# 7_Jetson_Nano_P3.net
KiCad netlist of a schematic drawn in Altium Designer
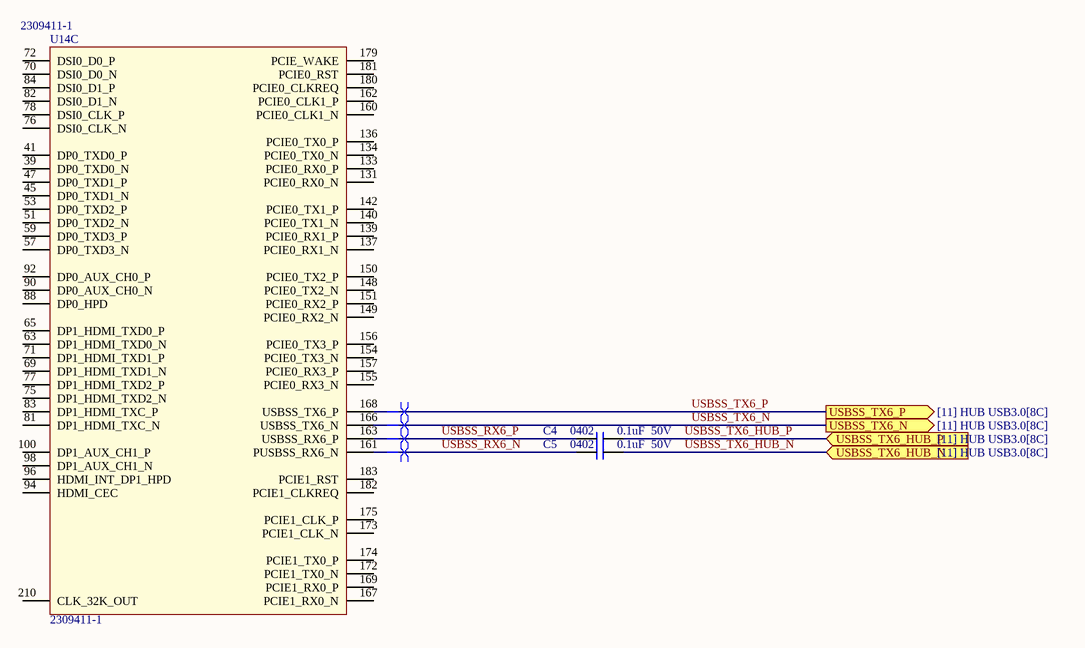
[diagram p0: [7] Jetson Nano P3.SchDoc]

(export (version "E")
  (design (tool "Eeschema 10.0.6"))
  (components
    (comp (ref "C4")
      (value "0.1uF")
      (footprint "C0402M")
      (description "CAP CER 0.1UF 50V X7R 0402")
      (fields
        (field (name "MANUFACTURER") "Murata")
        (field (name "MANUFACTURER PART NUMBER") "GRM155R71H104KE14D")
        (field (name "CASE/PACKAGE") "0402")
        (field (name "VOLTAGE") "50V")
      )
      (libsource (lib "CommonLib") (part "CAP_CER"))
    )
    (comp (ref "C5")
      (value "0.1uF")
      (footprint "C0402M")
      (description "CAP CER 0.1UF 50V X7R 0402")
      (fields
        (field (name "MANUFACTURER") "Murata")
        (field (name "MANUFACTURER PART NUMBER") "GRM155R71H104KE14D")
        (field (name "CASE/PACKAGE") "0402")
        (field (name "VOLTAGE") "50V")
      )
      (libsource (lib "CommonLib") (part "CAP_CER"))
    )
    (comp (ref "U14")
      (value "2309411-1")
      (footprint "2309411-1")
      (description "DDR4 SODIMM 260P 8.0H STD")
      (fields
        (field (name "MANUFACTURER") "TE Connectivity")
        (field (name "SUPPLIER PART NUMBER 1") "2309411-1")
      )
      (libsource (lib "Nauvus") (part "Jetson Nano SODIMM"))
    )
  )
  (nets
    (net (code "1") (name "/USBSS_RX6_N") (class "Default")
      (node (ref "C5") (pin "1") (pinfunction "1_1") (pintype "passive"))
      (node (ref "U14") (pin "161") (pinfunction "PUSBSS_RX6_N_161") (pintype "passive"))
    )
    (net (code "2") (name "/USBSS_RX6_P") (class "Default")
      (node (ref "C4") (pin "1") (pinfunction "1_1") (pintype "passive"))
      (node (ref "U14") (pin "163") (pinfunction "USBSS_RX6_P_163") (pintype "passive"))
    )
    (net (code "3") (name "/USBSS_TX6_HUB_N") (class "Default")
      (node (ref "C5") (pin "2") (pinfunction "2_2") (pintype "passive"))
    )
    (net (code "4") (name "/USBSS_TX6_HUB_P") (class "Default")
      (node (ref "C4") (pin "2") (pinfunction "2_2") (pintype "passive"))
    )
    (net (code "5") (name "/USBSS_TX6_N") (class "Default")
      (node (ref "U14") (pin "166") (pinfunction "USBSS_TX6_N_166") (pintype "passive"))
    )
    (net (code "6") (name "/USBSS_TX6_P") (class "Default")
      (node (ref "U14") (pin "168") (pinfunction "USBSS_TX6_P_168") (pintype "passive"))
    )
    (net (code "7") (name "unconnected-(U14C-CLK_32K_OUT-Pad210)") (class "Default")
      (node (ref "U14") (pin "210") (pinfunction "CLK_32K_OUT_210") (pintype "passive"))
    )
    (net (code "8") (name "unconnected-(U14C-DP0_AUX_CH0_N-Pad90)") (class "Default")
      (node (ref "U14") (pin "90") (pinfunction "DP0_AUX_CH0_N_90") (pintype "passive"))
    )
    (net (code "9") (name "unconnected-(U14C-DP0_AUX_CH0_P-Pad92)") (class "Default")
      (node (ref "U14") (pin "92") (pinfunction "DP0_AUX_CH0_P_92") (pintype "passive"))
    )
    (net (code "10") (name "unconnected-(U14C-DP0_HPD-Pad88)") (class "Default")
      (node (ref "U14") (pin "88") (pinfunction "DP0_HPD_88") (pintype "passive"))
    )
    (net (code "11") (name "unconnected-(U14C-DP0_TXD0_N-Pad39)") (class "Default")
      (node (ref "U14") (pin "39") (pinfunction "DP0_TXD0_N_39") (pintype "passive"))
    )
    (net (code "12") (name "unconnected-(U14C-DP0_TXD0_P-Pad41)") (class "Default")
      (node (ref "U14") (pin "41") (pinfunction "DP0_TXD0_P_41") (pintype "passive"))
    )
    (net (code "13") (name "unconnected-(U14C-DP0_TXD1_N-Pad45)") (class "Default")
      (node (ref "U14") (pin "45") (pinfunction "DP0_TXD1_N_45") (pintype "passive"))
    )
    (net (code "14") (name "unconnected-(U14C-DP0_TXD1_P-Pad47)") (class "Default")
      (node (ref "U14") (pin "47") (pinfunction "DP0_TXD1_P_47") (pintype "passive"))
    )
    (net (code "15") (name "unconnected-(U14C-DP0_TXD2_N-Pad51)") (class "Default")
      (node (ref "U14") (pin "51") (pinfunction "DP0_TXD2_N_51") (pintype "passive"))
    )
    (net (code "16") (name "unconnected-(U14C-DP0_TXD2_P-Pad53)") (class "Default")
      (node (ref "U14") (pin "53") (pinfunction "DP0_TXD2_P_53") (pintype "passive"))
    )
    (net (code "17") (name "unconnected-(U14C-DP0_TXD3_N-Pad57)") (class "Default")
      (node (ref "U14") (pin "57") (pinfunction "DP0_TXD3_N_57") (pintype "passive"))
    )
    (net (code "18") (name "unconnected-(U14C-DP0_TXD3_P-Pad59)") (class "Default")
      (node (ref "U14") (pin "59") (pinfunction "DP0_TXD3_P_59") (pintype "passive"))
    )
    (net (code "19") (name "unconnected-(U14C-DP1_AUX_CH1_N-Pad98)") (class "Default")
      (node (ref "U14") (pin "98") (pinfunction "DP1_AUX_CH1_N_98") (pintype "passive"))
    )
    (net (code "20") (name "unconnected-(U14C-DP1_AUX_CH1_P-Pad100)") (class "Default")
      (node (ref "U14") (pin "100") (pinfunction "DP1_AUX_CH1_P_100") (pintype "passive"))
    )
    (net (code "21") (name "unconnected-(U14C-DP1_HDMI_TXC_N-Pad81)") (class "Default")
      (node (ref "U14") (pin "81") (pinfunction "DP1_HDMI_TXC_N_81") (pintype "passive"))
    )
    (net (code "22") (name "unconnected-(U14C-DP1_HDMI_TXC_P-Pad83)") (class "Default")
      (node (ref "U14") (pin "83") (pinfunction "DP1_HDMI_TXC_P_83") (pintype "passive"))
    )
    (net (code "23") (name "unconnected-(U14C-DP1_HDMI_TXD0_N-Pad63)") (class "Default")
      (node (ref "U14") (pin "63") (pinfunction "DP1_HDMI_TXD0_N_63") (pintype "passive"))
    )
    (net (code "24") (name "unconnected-(U14C-DP1_HDMI_TXD0_P-Pad65)") (class "Default")
      (node (ref "U14") (pin "65") (pinfunction "DP1_HDMI_TXD0_P_65") (pintype "passive"))
    )
    (net (code "25") (name "unconnected-(U14C-DP1_HDMI_TXD1_N-Pad69)") (class "Default")
      (node (ref "U14") (pin "69") (pinfunction "DP1_HDMI_TXD1_N_69") (pintype "passive"))
    )
    (net (code "26") (name "unconnected-(U14C-DP1_HDMI_TXD1_P-Pad71)") (class "Default")
      (node (ref "U14") (pin "71") (pinfunction "DP1_HDMI_TXD1_P_71") (pintype "passive"))
    )
    (net (code "27") (name "unconnected-(U14C-DP1_HDMI_TXD2_N-Pad75)") (class "Default")
      (node (ref "U14") (pin "75") (pinfunction "DP1_HDMI_TXD2_N_75") (pintype "passive"))
    )
    (net (code "28") (name "unconnected-(U14C-DP1_HDMI_TXD2_P-Pad77)") (class "Default")
      (node (ref "U14") (pin "77") (pinfunction "DP1_HDMI_TXD2_P_77") (pintype "passive"))
    )
    (net (code "29") (name "unconnected-(U14C-DSI0_CLK_N-Pad76)") (class "Default")
      (node (ref "U14") (pin "76") (pinfunction "DSI0_CLK_N_76") (pintype "passive"))
    )
    (net (code "30") (name "unconnected-(U14C-DSI0_CLK_P-Pad78)") (class "Default")
      (node (ref "U14") (pin "78") (pinfunction "DSI0_CLK_P_78") (pintype "passive"))
    )
    (net (code "31") (name "unconnected-(U14C-DSI0_D0_N-Pad70)") (class "Default")
      (node (ref "U14") (pin "70") (pinfunction "DSI0_D0_N_70") (pintype "passive"))
    )
    (net (code "32") (name "unconnected-(U14C-DSI0_D0_P-Pad72)") (class "Default")
      (node (ref "U14") (pin "72") (pinfunction "DSI0_D0_P_72") (pintype "passive"))
    )
    (net (code "33") (name "unconnected-(U14C-DSI0_D1_N-Pad82)") (class "Default")
      (node (ref "U14") (pin "82") (pinfunction "DSI0_D1_N_82") (pintype "passive"))
    )
    (net (code "34") (name "unconnected-(U14C-DSI0_D1_P-Pad84)") (class "Default")
      (node (ref "U14") (pin "84") (pinfunction "DSI0_D1_P_84") (pintype "passive"))
    )
    (net (code "35") (name "unconnected-(U14C-HDMI_CEC-Pad94)") (class "Default")
      (node (ref "U14") (pin "94") (pinfunction "HDMI_CEC_94") (pintype "passive"))
    )
    (net (code "36") (name "unconnected-(U14C-HDMI_INT_DP1_HPD-Pad96)") (class "Default")
      (node (ref "U14") (pin "96") (pinfunction "HDMI_INT_DP1_HPD_96") (pintype "passive"))
    )
    (net (code "37") (name "unconnected-(U14C-PCIE0_CLK1_N-Pad160)") (class "Default")
      (node (ref "U14") (pin "160") (pinfunction "PCIE0_CLK1_N_160") (pintype "passive"))
    )
    (net (code "38") (name "unconnected-(U14C-PCIE0_CLK1_P-Pad162)") (class "Default")
      (node (ref "U14") (pin "162") (pinfunction "PCIE0_CLK1_P_162") (pintype "passive"))
    )
    (net (code "39") (name "unconnected-(U14C-PCIE0_CLKREQ-Pad180)") (class "Default")
      (node (ref "U14") (pin "180") (pinfunction "PCIE0_CLKREQ_180") (pintype "passive"))
    )
    (net (code "40") (name "unconnected-(U14C-PCIE0_RST-Pad181)") (class "Default")
      (node (ref "U14") (pin "181") (pinfunction "PCIE0_RST_181") (pintype "passive"))
    )
    (net (code "41") (name "unconnected-(U14C-PCIE0_RX0_N-Pad131)") (class "Default")
      (node (ref "U14") (pin "131") (pinfunction "PCIE0_RX0_N_131") (pintype "passive"))
    )
    (net (code "42") (name "unconnected-(U14C-PCIE0_RX0_P-Pad133)") (class "Default")
      (node (ref "U14") (pin "133") (pinfunction "PCIE0_RX0_P_133") (pintype "passive"))
    )
    (net (code "43") (name "unconnected-(U14C-PCIE0_RX1_N-Pad137)") (class "Default")
      (node (ref "U14") (pin "137") (pinfunction "PCIE0_RX1_N_137") (pintype "passive"))
    )
    (net (code "44") (name "unconnected-(U14C-PCIE0_RX1_P-Pad139)") (class "Default")
      (node (ref "U14") (pin "139") (pinfunction "PCIE0_RX1_P_139") (pintype "passive"))
    )
    (net (code "45") (name "unconnected-(U14C-PCIE0_RX2_N-Pad149)") (class "Default")
      (node (ref "U14") (pin "149") (pinfunction "PCIE0_RX2_N_149") (pintype "passive"))
    )
    (net (code "46") (name "unconnected-(U14C-PCIE0_RX2_P-Pad151)") (class "Default")
      (node (ref "U14") (pin "151") (pinfunction "PCIE0_RX2_P_151") (pintype "passive"))
    )
    (net (code "47") (name "unconnected-(U14C-PCIE0_RX3_N-Pad155)") (class "Default")
      (node (ref "U14") (pin "155") (pinfunction "PCIE0_RX3_N_155") (pintype "passive"))
    )
    (net (code "48") (name "unconnected-(U14C-PCIE0_RX3_P-Pad157)") (class "Default")
      (node (ref "U14") (pin "157") (pinfunction "PCIE0_RX3_P_157") (pintype "passive"))
    )
    (net (code "49") (name "unconnected-(U14C-PCIE0_TX0_N-Pad134)") (class "Default")
      (node (ref "U14") (pin "134") (pinfunction "PCIE0_TX0_N_134") (pintype "passive"))
    )
    (net (code "50") (name "unconnected-(U14C-PCIE0_TX0_P-Pad136)") (class "Default")
      (node (ref "U14") (pin "136") (pinfunction "PCIE0_TX0_P_136") (pintype "passive"))
    )
    (net (code "51") (name "unconnected-(U14C-PCIE0_TX1_N-Pad140)") (class "Default")
      (node (ref "U14") (pin "140") (pinfunction "PCIE0_TX1_N_140") (pintype "passive"))
    )
    (net (code "52") (name "unconnected-(U14C-PCIE0_TX1_P-Pad142)") (class "Default")
      (node (ref "U14") (pin "142") (pinfunction "PCIE0_TX1_P_142") (pintype "passive"))
    )
    (net (code "53") (name "unconnected-(U14C-PCIE0_TX2_N-Pad148)") (class "Default")
      (node (ref "U14") (pin "148") (pinfunction "PCIE0_TX2_N_148") (pintype "passive"))
    )
    (net (code "54") (name "unconnected-(U14C-PCIE0_TX2_P-Pad150)") (class "Default")
      (node (ref "U14") (pin "150") (pinfunction "PCIE0_TX2_P_150") (pintype "passive"))
    )
    (net (code "55") (name "unconnected-(U14C-PCIE0_TX3_N-Pad154)") (class "Default")
      (node (ref "U14") (pin "154") (pinfunction "PCIE0_TX3_N_154") (pintype "passive"))
    )
    (net (code "56") (name "unconnected-(U14C-PCIE0_TX3_P-Pad156)") (class "Default")
      (node (ref "U14") (pin "156") (pinfunction "PCIE0_TX3_P_156") (pintype "passive"))
    )
    (net (code "57") (name "unconnected-(U14C-PCIE1_CLKREQ-Pad182)") (class "Default")
      (node (ref "U14") (pin "182") (pinfunction "PCIE1_CLKREQ_182") (pintype "passive"))
    )
    (net (code "58") (name "unconnected-(U14C-PCIE1_CLK_N-Pad173)") (class "Default")
      (node (ref "U14") (pin "173") (pinfunction "PCIE1_CLK_N_173") (pintype "passive"))
    )
    (net (code "59") (name "unconnected-(U14C-PCIE1_CLK_P-Pad175)") (class "Default")
      (node (ref "U14") (pin "175") (pinfunction "PCIE1_CLK_P_175") (pintype "passive"))
    )
    (net (code "60") (name "unconnected-(U14C-PCIE1_RST-Pad183)") (class "Default")
      (node (ref "U14") (pin "183") (pinfunction "PCIE1_RST_183") (pintype "passive"))
    )
    (net (code "61") (name "unconnected-(U14C-PCIE1_RX0_N-Pad167)") (class "Default")
      (node (ref "U14") (pin "167") (pinfunction "PCIE1_RX0_N_167") (pintype "passive"))
    )
    (net (code "62") (name "unconnected-(U14C-PCIE1_RX0_P-Pad169)") (class "Default")
      (node (ref "U14") (pin "169") (pinfunction "PCIE1_RX0_P_169") (pintype "passive"))
    )
    (net (code "63") (name "unconnected-(U14C-PCIE1_TX0_N-Pad172)") (class "Default")
      (node (ref "U14") (pin "172") (pinfunction "PCIE1_TX0_N_172") (pintype "passive"))
    )
    (net (code "64") (name "unconnected-(U14C-PCIE1_TX0_P-Pad174)") (class "Default")
      (node (ref "U14") (pin "174") (pinfunction "PCIE1_TX0_P_174") (pintype "passive"))
    )
    (net (code "65") (name "unconnected-(U14C-PCIE_WAKE-Pad179)") (class "Default")
      (node (ref "U14") (pin "179") (pinfunction "PCIE_WAKE_179") (pintype "passive"))
    )
  )
)
